# power_supply.net
KiCad netlist of a schematic drawn in Altium Designer
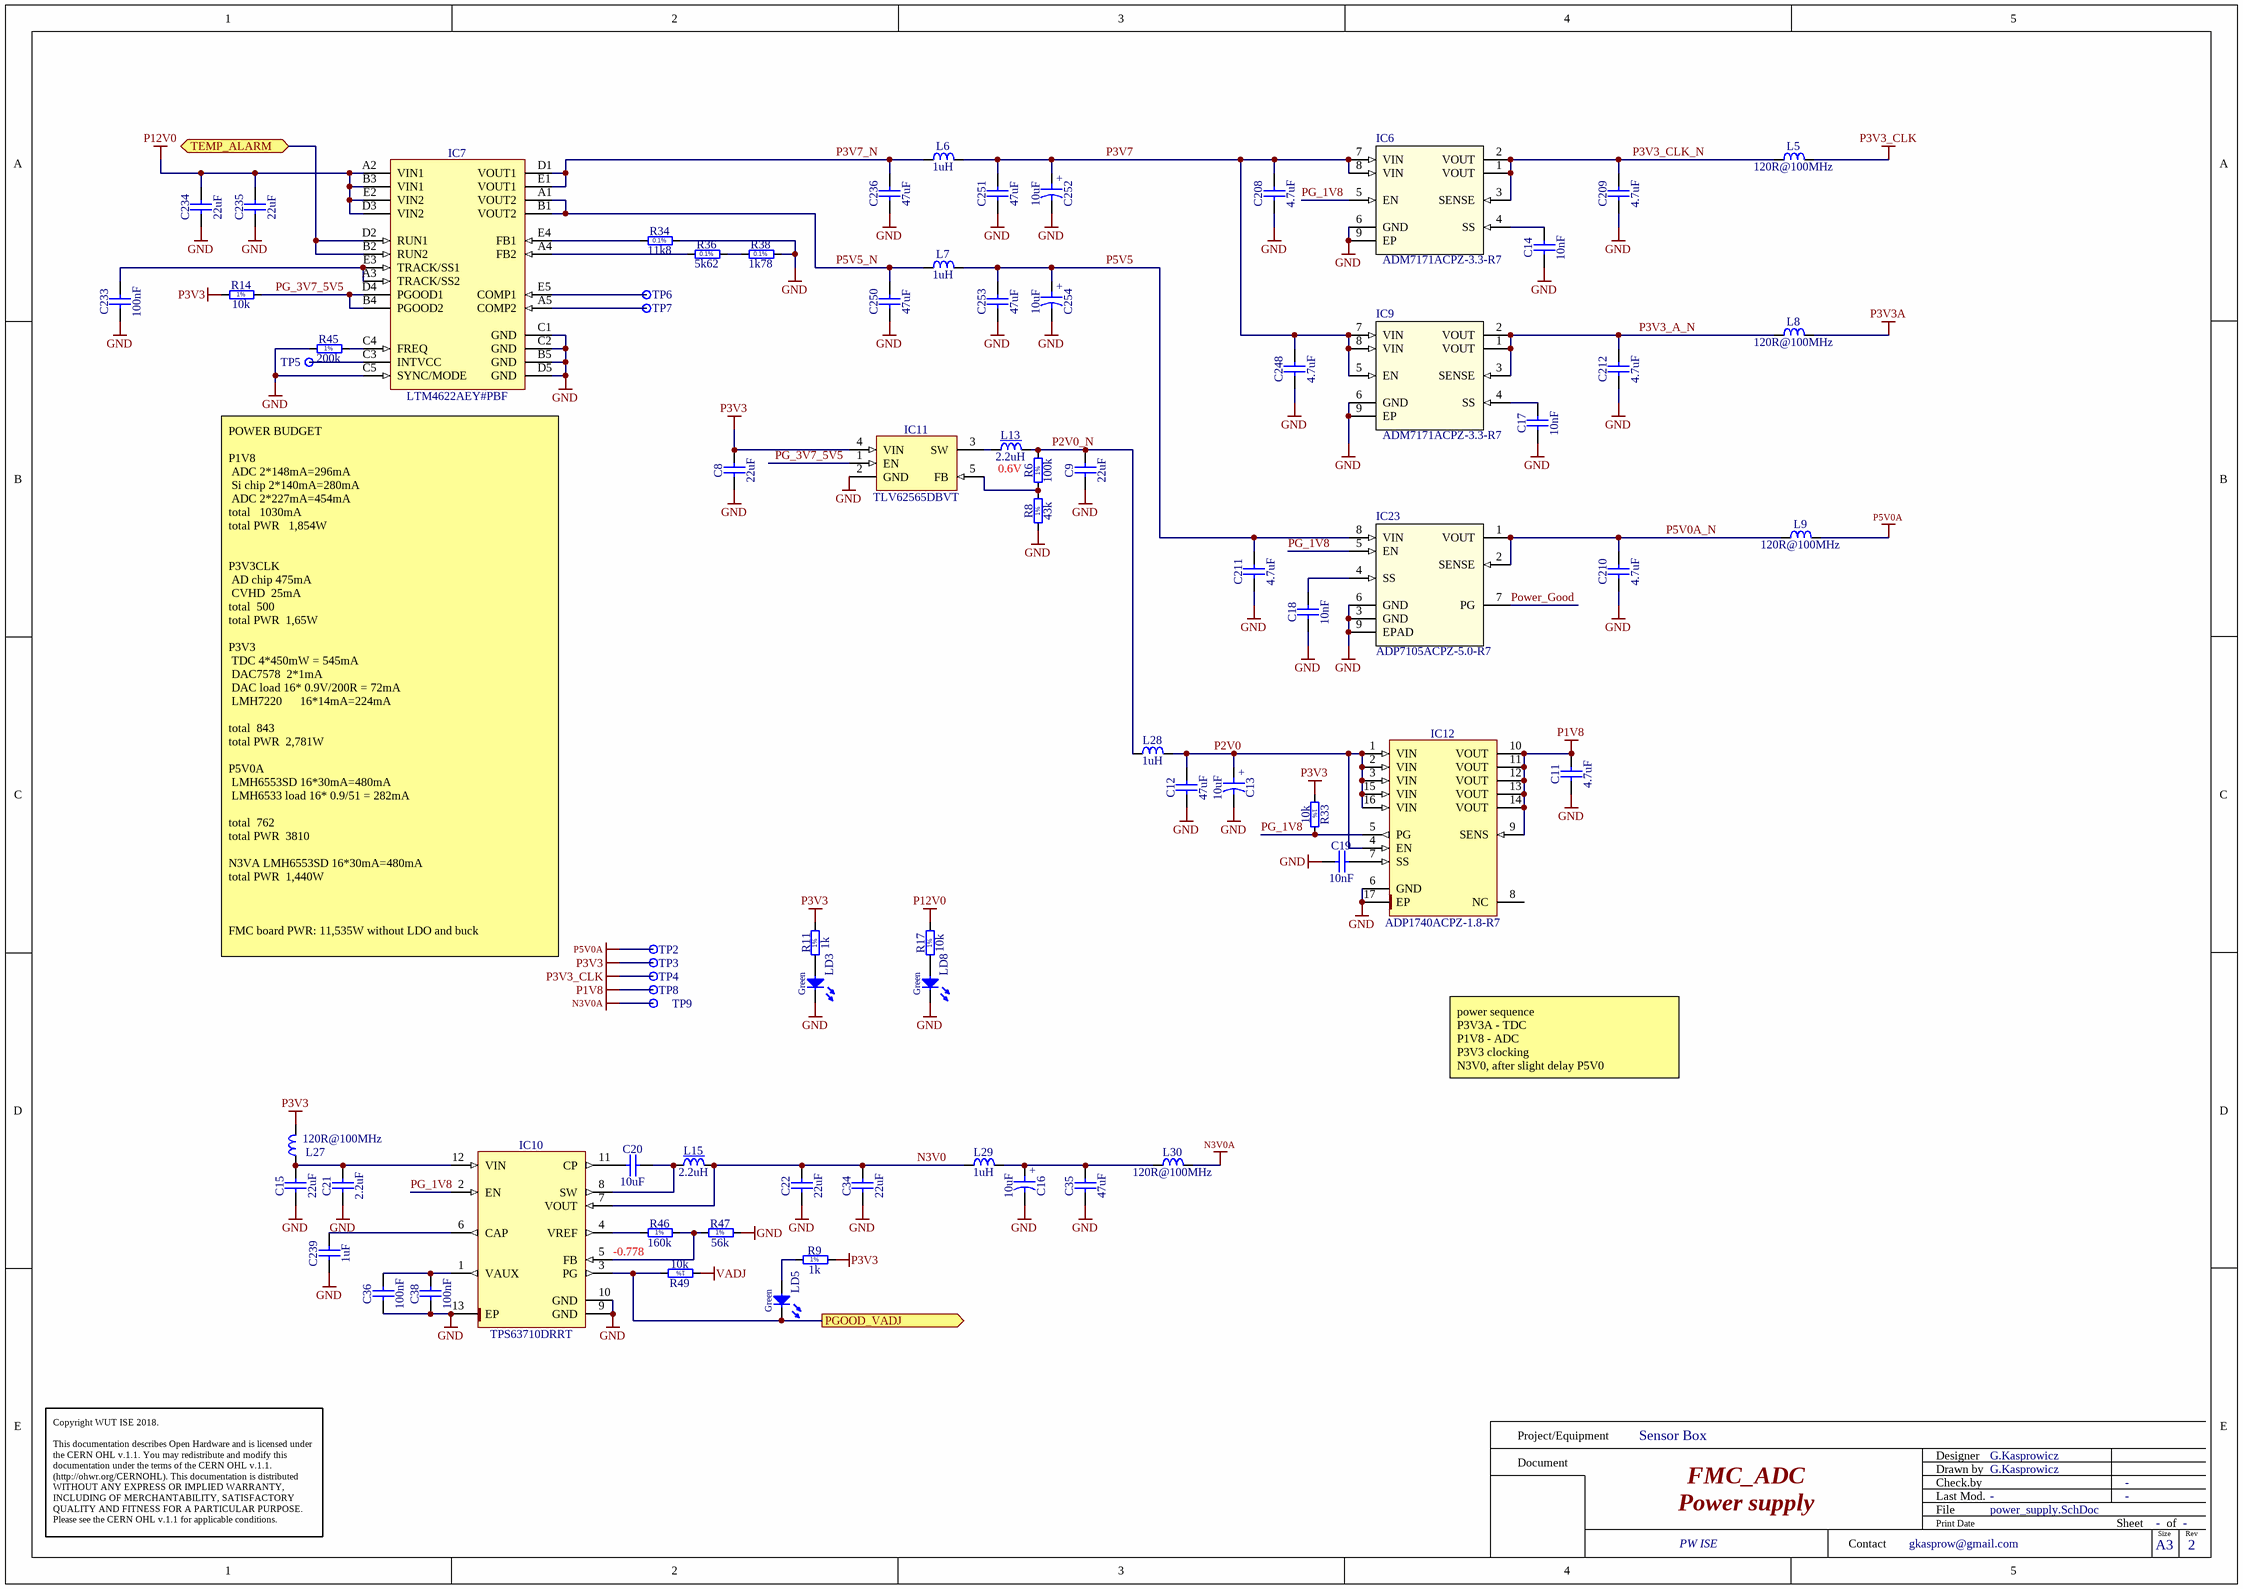
[diagram p0: power_supply.SchDoc]

(export (version "E")
  (design (tool "Eeschema 10.0.6"))
  (components
    (comp (ref "C8")
      (value "22uF")
      (footprint "CAPC2012X135N")
      (description "Non-polarised capacitor")
      (fields
        (field (name "PART NUMBER") "CC0805_22UF_16V_10%_X5R")
        (field (name "VOLTAGE") "16V")
        (field (name "AUTHOR") "CERN DEM JLC")
      )
      (libsource (lib "Capacitors") (part "Capacitor - non polarized"))
    )
    (comp (ref "C9")
      (value "22uF")
      (footprint "CAPC2012X135N")
      (description "Non-polarised capacitor")
      (fields
        (field (name "PART NUMBER") "CC0805_22UF_16V_10%_X5R")
        (field (name "VOLTAGE") "16V")
        (field (name "AUTHOR") "CERN DEM JLC")
      )
      (libsource (lib "Capacitors") (part "Capacitor - non polarized"))
    )
    (comp (ref "C11")
      (value "4.7uF")
      (footprint "CAPC1709X95N")
      (description "Non-polarised capacitor")
      (fields
        (field (name "PART NUMBER") "CC0603_4.7UF_16V_10%_X5R")
        (field (name "VOLTAGE") "16V")
        (field (name "AUTHOR") "CERN DEM JLC")
      )
      (libsource (lib "Capacitors") (part "Capacitor - non polarized"))
    )
    (comp (ref "C12")
      (value "47uF")
      (footprint "CAPC3225X270N")
      (description "Non-polarised capacitor")
      (fields
        (field (name "PART NUMBER") "CC1210_47UF_10V_20%_X5R")
        (field (name "VOLTAGE") "10V")
        (field (name "AUTHOR") "CERN DEM JLC")
      )
      (libsource (lib "Capacitors") (part "Capacitor - non polarized"))
    )
    (comp (ref "C13")
      (value "10uF")
      (footprint "CAPMP3216X180N")
      (description "Polarised capacitor")
      (fields
        (field (name "PART NUMBER") "CTE3216-18_10UF_10V_10%_LESR1800")
        (field (name "VOLTAGE") "10V")
        (field (name "AUTHOR") "CERN DEM JLC")
      )
      (libsource (lib "Capacitors") (part "Capacitor - polarized"))
    )
    (comp (ref "C14")
      (value "10nF")
      (footprint "CAPC1005X55N")
      (description "Non-polarised capacitor")
      (fields
        (field (name "PART NUMBER") "CC0402_10NF_16V_10%_X7R")
        (field (name "VOLTAGE") "16V")
        (field (name "AUTHOR") "CERN DEM JLC")
      )
      (libsource (lib "Capacitors") (part "Capacitor - non polarized"))
    )
    (comp (ref "C15")
      (value "22uF")
      (footprint "CAPC2012X135N")
      (description "Non-polarised capacitor")
      (fields
        (field (name "PART NUMBER") "CC0805_22UF_16V_10%_X5R")
        (field (name "VOLTAGE") "16V")
        (field (name "AUTHOR") "CERN DEM JLC")
      )
      (libsource (lib "Capacitors") (part "Capacitor - non polarized"))
    )
    (comp (ref "C16")
      (value "10uF")
      (footprint "CAPMP3216X180N")
      (description "Polarised capacitor")
      (fields
        (field (name "PART NUMBER") "CTE3216-18_10UF_10V_10%_LESR1800")
        (field (name "VOLTAGE") "10V")
        (field (name "AUTHOR") "CERN DEM JLC")
      )
      (libsource (lib "Capacitors") (part "Capacitor - polarized"))
    )
    (comp (ref "C17")
      (value "10nF")
      (footprint "CAPC1005X55N")
      (description "Non-polarised capacitor")
      (fields
        (field (name "PART NUMBER") "CC0402_10NF_16V_10%_X7R")
        (field (name "VOLTAGE") "16V")
        (field (name "AUTHOR") "CERN DEM JLC")
      )
      (libsource (lib "Capacitors") (part "Capacitor - non polarized"))
    )
    (comp (ref "C18")
      (value "10nF")
      (footprint "CAPC1005X55N")
      (description "Non-polarised capacitor")
      (fields
        (field (name "PART NUMBER") "CC0402_10NF_16V_10%_X7R")
        (field (name "VOLTAGE") "16V")
        (field (name "AUTHOR") "CERN DEM JLC")
      )
      (libsource (lib "Capacitors") (part "Capacitor - non polarized"))
    )
    (comp (ref "C19")
      (value "10nF")
      (footprint "CAPC1005X55N")
      (description "Non-polarised capacitor")
      (fields
        (field (name "PART NUMBER") "CC0402_10NF_16V_10%_X7R")
        (field (name "VOLTAGE") "16V")
        (field (name "AUTHOR") "CERN DEM JLC")
      )
      (libsource (lib "Capacitors") (part "Capacitor - non polarized"))
    )
    (comp (ref "C20")
      (value "10uF")
      (footprint "CAPC2012X135N")
      (description "Non-polarised capacitor")
      (fields
        (field (name "PART NUMBER") "CC0805_10UF_16V_10%_X5R")
        (field (name "VOLTAGE") "16V")
        (field (name "AUTHOR") "CERN DEM JLC")
      )
      (libsource (lib "Capacitors") (part "Capacitor - non polarized"))
    )
    (comp (ref "C21")
      (value "2.2uF")
      (footprint "CAPC1608X87N")
      (description "Non-polarised capacitor")
      (fields
        (field (name "PART NUMBER") "CC0603_2.2UF_16V_10%_X5R")
        (field (name "VOLTAGE") "16V")
        (field (name "AUTHOR") "CERN DEM JLC")
      )
      (libsource (lib "Capacitors") (part "Capacitor - non polarized"))
    )
    (comp (ref "C22")
      (value "22uF")
      (footprint "CAPC2012X135N")
      (description "Non-polarised capacitor")
      (fields
        (field (name "PART NUMBER") "CC0805_22UF_16V_10%_X5R")
        (field (name "VOLTAGE") "16V")
        (field (name "AUTHOR") "CERN DEM JLC")
      )
      (libsource (lib "Capacitors") (part "Capacitor - non polarized"))
    )
    (comp (ref "C34")
      (value "22uF")
      (footprint "CAPC2012X135N")
      (description "Non-polarised capacitor")
      (fields
        (field (name "PART NUMBER") "CC0805_22UF_16V_10%_X5R")
        (field (name "VOLTAGE") "16V")
        (field (name "AUTHOR") "CERN DEM JLC")
      )
      (libsource (lib "Capacitors") (part "Capacitor - non polarized"))
    )
    (comp (ref "C35")
      (value "47uF")
      (footprint "CAPC3225X270N")
      (description "Non-polarised capacitor")
      (fields
        (field (name "PART NUMBER") "CC1210_47UF_10V_20%_X5R")
        (field (name "VOLTAGE") "10V")
        (field (name "AUTHOR") "CERN DEM JLC")
      )
      (libsource (lib "Capacitors") (part "Capacitor - non polarized"))
    )
    (comp (ref "C36")
      (value "100nF")
      (footprint "CAPC1005X55N")
      (description "Non-polarised capacitor")
      (fields
        (field (name "PART NUMBER") "CC0402_100NF_16V_10%_X5R")
        (field (name "VOLTAGE") "16V")
        (field (name "AUTHOR") "CERN DEM JLC")
      )
      (libsource (lib "Capacitors") (part "Capacitor - non polarized"))
    )
    (comp (ref "C38")
      (value "100nF")
      (footprint "CAPC1005X55N")
      (description "Non-polarised capacitor")
      (fields
        (field (name "PART NUMBER") "CC0402_100NF_16V_10%_X5R")
        (field (name "VOLTAGE") "16V")
        (field (name "AUTHOR") "CERN DEM JLC")
      )
      (libsource (lib "Capacitors") (part "Capacitor - non polarized"))
    )
    (comp (ref "C208")
      (value "4.7uF")
      (footprint "CAPC1709X95N")
      (description "Non-polarised capacitor")
      (fields
        (field (name "PART NUMBER") "CC0603_4.7UF_16V_10%_X5R")
        (field (name "VOLTAGE") "16V")
        (field (name "AUTHOR") "CERN DEM JLC")
      )
      (libsource (lib "Capacitors") (part "Capacitor - non polarized"))
    )
    (comp (ref "C209")
      (value "4.7uF")
      (footprint "CAPC1709X95N")
      (description "Non-polarised capacitor")
      (fields
        (field (name "PART NUMBER") "CC0603_4.7UF_16V_10%_X5R")
        (field (name "VOLTAGE") "16V")
        (field (name "AUTHOR") "CERN DEM JLC")
      )
      (libsource (lib "Capacitors") (part "Capacitor - non polarized"))
    )
    (comp (ref "C210")
      (value "4.7uF")
      (footprint "CAPC1709X95N")
      (description "Non-polarised capacitor")
      (fields
        (field (name "PART NUMBER") "CC0603_4.7UF_16V_10%_X5R")
        (field (name "VOLTAGE") "16V")
        (field (name "AUTHOR") "CERN DEM JLC")
      )
      (libsource (lib "Capacitors") (part "Capacitor - non polarized"))
    )
    (comp (ref "C211")
      (value "4.7uF")
      (footprint "CAPC1709X95N")
      (description "Non-polarised capacitor")
      (fields
        (field (name "PART NUMBER") "CC0603_4.7UF_16V_10%_X5R")
        (field (name "VOLTAGE") "16V")
        (field (name "AUTHOR") "CERN DEM JLC")
      )
      (libsource (lib "Capacitors") (part "Capacitor - non polarized"))
    )
    (comp (ref "C212")
      (value "4.7uF")
      (footprint "CAPC1709X95N")
      (description "Non-polarised capacitor")
      (fields
        (field (name "PART NUMBER") "CC0603_4.7UF_16V_10%_X5R")
        (field (name "VOLTAGE") "16V")
        (field (name "AUTHOR") "CERN DEM JLC")
      )
      (libsource (lib "Capacitors") (part "Capacitor - non polarized"))
    )
    (comp (ref "C233")
      (value "100nF")
      (footprint "CAPC1005X55N")
      (description "Non-polarised capacitor")
      (fields
        (field (name "PART NUMBER") "CC0402_100NF_16V_10%_X5R")
        (field (name "VOLTAGE") "16V")
        (field (name "AUTHOR") "CERN DEM JLC")
      )
      (libsource (lib "Capacitors") (part "Capacitor - non polarized"))
    )
    (comp (ref "C234")
      (value "22uF")
      (footprint "CAPC2012X135N")
      (description "Non-polarised capacitor")
      (fields
        (field (name "PART NUMBER") "CC0805_22UF_16V_10%_X5R")
        (field (name "VOLTAGE") "16V")
        (field (name "AUTHOR") "CERN DEM JLC")
      )
      (libsource (lib "Capacitors") (part "Capacitor - non polarized"))
    )
    (comp (ref "C235")
      (value "22uF")
      (footprint "CAPC2012X135N")
      (description "Non-polarised capacitor")
      (fields
        (field (name "PART NUMBER") "CC0805_22UF_16V_10%_X5R")
        (field (name "VOLTAGE") "16V")
        (field (name "AUTHOR") "CERN DEM JLC")
      )
      (libsource (lib "Capacitors") (part "Capacitor - non polarized"))
    )
    (comp (ref "C236")
      (value "47uF")
      (footprint "CAPC3225X270N")
      (description "Non-polarised capacitor")
      (fields
        (field (name "PART NUMBER") "CC1210_47UF_10V_20%_X5R")
        (field (name "VOLTAGE") "10V")
        (field (name "AUTHOR") "CERN DEM JLC")
      )
      (libsource (lib "Capacitors") (part "Capacitor - non polarized"))
    )
    (comp (ref "C239")
      (value "1uF")
      (footprint "CAPC1608X87N")
      (description "Non-polarised capacitor")
      (fields
        (field (name "PART NUMBER") "CC0603_1UF_16V_10%_X7R")
        (field (name "VOLTAGE") "16V")
        (field (name "AUTHOR") "CERN DEM JLC")
      )
      (libsource (lib "Capacitors") (part "Capacitor - non polarized"))
    )
    (comp (ref "C248")
      (value "4.7uF")
      (footprint "CAPC1709X95N")
      (description "Non-polarised capacitor")
      (fields
        (field (name "PART NUMBER") "CC0603_4.7UF_16V_10%_X5R")
        (field (name "VOLTAGE") "16V")
        (field (name "AUTHOR") "CERN DEM JLC")
      )
      (libsource (lib "Capacitors") (part "Capacitor - non polarized"))
    )
    (comp (ref "C250")
      (value "47uF")
      (footprint "CAPC3225X270N")
      (description "Non-polarised capacitor")
      (fields
        (field (name "PART NUMBER") "CC1210_47UF_10V_20%_X5R")
        (field (name "VOLTAGE") "10V")
        (field (name "AUTHOR") "CERN DEM JLC")
      )
      (libsource (lib "Capacitors") (part "Capacitor - non polarized"))
    )
    (comp (ref "C251")
      (value "47uF")
      (footprint "CAPC3225X270N")
      (description "Non-polarised capacitor")
      (fields
        (field (name "PART NUMBER") "CC1210_47UF_10V_20%_X5R")
        (field (name "VOLTAGE") "10V")
        (field (name "AUTHOR") "CERN DEM JLC")
      )
      (libsource (lib "Capacitors") (part "Capacitor - non polarized"))
    )
    (comp (ref "C252")
      (value "10uF")
      (footprint "CAPMP3216X180N")
      (description "Polarised capacitor")
      (fields
        (field (name "PART NUMBER") "CTE3216-18_10UF_10V_10%_LESR1800")
        (field (name "VOLTAGE") "10V")
        (field (name "AUTHOR") "CERN DEM JLC")
      )
      (libsource (lib "Capacitors") (part "Capacitor - polarized"))
    )
    (comp (ref "C253")
      (value "47uF")
      (footprint "CAPC3225X270N")
      (description "Non-polarised capacitor")
      (fields
        (field (name "PART NUMBER") "CC1210_47UF_10V_20%_X5R")
        (field (name "VOLTAGE") "10V")
        (field (name "AUTHOR") "CERN DEM JLC")
      )
      (libsource (lib "Capacitors") (part "Capacitor - non polarized"))
    )
    (comp (ref "C254")
      (value "10uF")
      (footprint "CAPMP3216X180N")
      (description "Polarised capacitor")
      (fields
        (field (name "PART NUMBER") "CTE3216-18_10UF_10V_10%_LESR1800")
        (field (name "VOLTAGE") "10V")
        (field (name "AUTHOR") "CERN DEM JLC")
      )
      (libsource (lib "Capacitors") (part "Capacitor - polarized"))
    )
    (comp (ref "IC6")
      (value "ADM7171ACPZ-3.3-R7")
      (footprint "CP_8_21-L")
      (description "6.5 V, 1 A, Ultralow Noise, High PSRR,  Fast Transient Response CMOS LDO")
      (fields (field (name "MANUFACTURER") "Analog Devices"))
      (libsource (lib "FMC_ADC") (part "ADM7171ACPZ-3.3-R7"))
    )
    (comp (ref "IC7")
      (value "LTM4622AEY#PBF")
      (footprint "BGA25C127P5X5_625X625X262")
      (description "3.6V-20V To 1.5V-12V, Dual 2A or Single 4A  Ultrathin Step-Down DC/DC µModule Regulator")
      (fields (field (name "MANUFACTURER") "LINEAR TECHNOLOGY") (field (name "AUTHOR") "CERN DEM MR"))
      (libsource (lib "ICs And Semiconductors") (part "LTM4622A"))
    )
    (comp (ref "IC9")
      (value "ADM7171ACPZ-3.3-R7")
      (footprint "CP_8_21-L")
      (description "6.5 V, 1 A, Ultralow Noise, High PSRR,  Fast Transient Response CMOS LDO")
      (fields (field (name "MANUFACTURER") "Analog Devices"))
      (libsource (lib "FMC_ADC") (part "ADM7171ACPZ-3.3-R7"))
    )
    (comp (ref "IC10")
      (value "TPS63710DRRT")
      (footprint "SON50P300X80_HS-13N")
      (description "Low Noise, 1A Synchronous Inverting Buck Converter in 3x3 WSON Package")
      (fields (field (name "MANUFACTURER") "TEXAS INSTRUMENTS") (field (name "AUTHOR") "GK"))
      (libsource (lib "LIBRARY_SCH") (part "PM_TPS6371"))
    )
    (comp (ref "IC11")
      (value "TLV62565DBVT")
      (footprint "SOT95P280X145-5N")
      (description "1.5A High Efficiency Step-Down Converter, Adjustable Output Voltage")
      (fields (field (name "MANUFACTURER") "TEXAS INSTRUMENTS") (field (name "AUTHOR") "CERN DEM JMW"))
      (libsource (lib "ICs And Semiconductors") (part "TLV62565"))
    )
    (comp (ref "IC12")
      (value "ADP1740ACPZ-1.8-R7")
      (footprint "QFN65P400X400X100-17N-S225")
      (description "2A, Low-Dropout Linear Regulator")
      (fields (field (name "MANUFACTURER") "ANALOG DEVICES") (field (name "AUTHOR") "CERN DEM JLC"))
      (libsource (lib "ICs And Semiconductors") (part "ADP1740"))
    )
    (comp (ref "IC23")
      (value "ADP7105ACPZ-5.0-R7")
      (footprint "CP_8_5")
      (description "20 V, 500 mA, Low Noise LDO Regulator  with Soft Start")
      (fields (field (name "MANUFACTURER") "Analog Devices"))
      (libsource (lib "FMC_ADC") (part "ADP7105ACPZ-5.0-R7"))
    )
    (comp (ref "L5")
      (value "120R@100MHz")
      (footprint "INDC1608X65N")
      (description "Inductor")
      (fields
        (field (name "PART NUMBER") "IND0603_MURATA_BLM18SG121TN1D")
        (field (name "POWER") "3A")
        (field (name "AUTHOR") "CERN DEM JLC")
      )
      (libsource (lib "Inductors & Transformers") (part "Inductor"))
    )
    (comp (ref "L6")
      (value "1uH")
      (footprint "INDC2620X100N")
      (description "Inductor")
      (fields
        (field (name "PART NUMBER") "IND1008_1UH_20%_WURTH_74479787210B")
        (field (name "POWER") "1.95A")
        (field (name "AUTHOR") "CERN DEM JLC")
      )
      (libsource (lib "Inductors & Transformers") (part "Inductor"))
    )
    (comp (ref "L7")
      (value "1uH")
      (footprint "INDC2620X100N")
      (description "Inductor")
      (fields
        (field (name "PART NUMBER") "IND1008_1UH_20%_WURTH_74479787210B")
        (field (name "POWER") "1.95A")
        (field (name "AUTHOR") "CERN DEM JLC")
      )
      (libsource (lib "Inductors & Transformers") (part "Inductor"))
    )
    (comp (ref "L8")
      (value "120R@100MHz")
      (footprint "INDC1608X65N")
      (description "Inductor")
      (fields
        (field (name "PART NUMBER") "IND0603_MURATA_BLM18SG121TN1D")
        (field (name "POWER") "3A")
        (field (name "AUTHOR") "CERN DEM JLC")
      )
      (libsource (lib "Inductors & Transformers") (part "Inductor"))
    )
    (comp (ref "L9")
      (value "120R@100MHz")
      (footprint "INDC1608X65N")
      (description "Inductor")
      (fields
        (field (name "PART NUMBER") "IND0603_MURATA_BLM18SG121TN1D")
        (field (name "POWER") "3A")
        (field (name "AUTHOR") "CERN DEM JLC")
      )
      (libsource (lib "Inductors & Transformers") (part "Inductor"))
    )
    (comp (ref "L13")
      (value "2.2uH")
      (footprint "IND_WURTH_WE-TPC_4828")
      (description "Inductor With Core")
      (fields
        (field (name "PART NUMBER") "IND_2.2UH_30%_WURTH_WE-TPC_7440430022")
        (field (name "POWER") "2.5A")
        (field (name "AUTHOR") "CERN DEM JLC")
      )
      (libsource (lib "Inductors & Transformers") (part "Inductor With Magnetic core"))
    )
    (comp (ref "L15")
      (value "2.2uH")
      (footprint "IND_WURTH_WE-TPC_4828")
      (description "Inductor With Core")
      (fields
        (field (name "PART NUMBER") "IND_2.2UH_30%_WURTH_WE-TPC_7440430022")
        (field (name "POWER") "2.5A")
        (field (name "AUTHOR") "CERN DEM JLC")
      )
      (libsource (lib "Inductors & Transformers") (part "Inductor With Magnetic core"))
    )
    (comp (ref "L27")
      (value "120R@100MHz")
      (footprint "INDC1608X65N")
      (description "Inductor")
      (fields
        (field (name "PART NUMBER") "IND0603_MURATA_BLM18SG121TN1D")
        (field (name "POWER") "3A")
        (field (name "AUTHOR") "CERN DEM JLC")
      )
      (libsource (lib "") (part "Inductor_1"))
    )
    (comp (ref "L28")
      (value "1uH")
      (footprint "INDC2620X100N")
      (description "Inductor")
      (fields
        (field (name "PART NUMBER") "IND1008_1UH_20%_WURTH_74479787210B")
        (field (name "POWER") "1.95A")
        (field (name "AUTHOR") "CERN DEM JLC")
      )
      (libsource (lib "Inductors & Transformers") (part "Inductor"))
    )
    (comp (ref "L29")
      (value "1uH")
      (footprint "INDC2620X100N")
      (description "Inductor")
      (fields
        (field (name "PART NUMBER") "IND1008_1UH_20%_WURTH_74479787210B")
        (field (name "POWER") "1.95A")
        (field (name "AUTHOR") "CERN DEM JLC")
      )
      (libsource (lib "Inductors & Transformers") (part "Inductor"))
    )
    (comp (ref "L30")
      (value "120R@100MHz")
      (footprint "INDC1608X65N")
      (description "Inductor")
      (fields
        (field (name "PART NUMBER") "IND0603_MURATA_BLM18SG121TN1D")
        (field (name "POWER") "3A")
        (field (name "AUTHOR") "CERN DEM JLC")
      )
      (libsource (lib "Inductors & Transformers") (part "Inductor"))
    )
    (comp (ref "LD3")
      (value "Green")
      (footprint "LED_KINGBRIGHT_KPH-1608CGCK")
      (description "LED Green 1C 2A")
      (fields
        (field (name "PART NUMBER") "LED_KINGBRIGHT_KPH-1608CGCK")
        (field (name "MANUFACTURER") "KINGBRIGHT")
        (field (name "AUTHOR") "CERN DEM JLC")
      )
      (libsource (lib "ICs And Semiconductors") (part "LED Green 1C 2A"))
    )
    (comp (ref "LD5")
      (value "Green")
      (footprint "LED_KINGBRIGHT_KPH-1608CGCK")
      (description "LED Green 1C 2A")
      (fields
        (field (name "PART NUMBER") "LED_KINGBRIGHT_KPH-1608CGCK")
        (field (name "MANUFACTURER") "KINGBRIGHT")
        (field (name "AUTHOR") "CERN DEM JLC")
      )
      (libsource (lib "ICs And Semiconductors") (part "LED Green 1C 2A"))
    )
    (comp (ref "LD8")
      (value "Green")
      (footprint "LED_KINGBRIGHT_KPH-1608CGCK")
      (description "LED Green 1C 2A")
      (fields
        (field (name "PART NUMBER") "LED_KINGBRIGHT_KPH-1608CGCK")
        (field (name "MANUFACTURER") "KINGBRIGHT")
        (field (name "AUTHOR") "CERN DEM JLC")
      )
      (libsource (lib "ICs And Semiconductors") (part "LED Green 1C 2A"))
    )
    (comp (ref "R6")
      (value "100k")
      (footprint "RESC1005X40N")
      (description "Resistor - 1%")
      (fields
        (field (name "PART NUMBER") "R0402_100K_1%_0.0625W_100PPM")
        (field (name "POWER") "0.0625W")
        (field (name "AUTHOR") "CERN DEM JLC")
      )
      (libsource (lib "Resistors") (part "Resistor - 1%"))
    )
    (comp (ref "R8")
      (value "43k")
      (footprint "RESC1005X40N")
      (description "Resistor - 1%")
      (fields
        (field (name "PART NUMBER") "R0402_43K_1%_0.0625W_100PPM")
        (field (name "POWER") "0.0625W")
        (field (name "AUTHOR") "CERN DEM JLC")
      )
      (libsource (lib "Resistors") (part "Resistor - 1%"))
    )
    (comp (ref "R9")
      (value "1k")
      (footprint "RESC1005X40N")
      (description "Resistor - 1%")
      (fields
        (field (name "PART NUMBER") "R0402_1K_1%_0.0625W_100PPM")
        (field (name "POWER") "0.0625W")
        (field (name "AUTHOR") "CERN DEM JLC")
      )
      (libsource (lib "Resistors") (part "Resistor - 1%"))
    )
    (comp (ref "R11")
      (value "1k")
      (footprint "RESC1005X40N")
      (description "Resistor - 1%")
      (fields
        (field (name "PART NUMBER") "R0402_1K_1%_0.0625W_100PPM")
        (field (name "POWER") "0.0625W")
        (field (name "AUTHOR") "CERN DEM JLC")
      )
      (libsource (lib "Resistors") (part "Resistor - 1%"))
    )
    (comp (ref "R14")
      (value "10k")
      (footprint "RESC1005X40N")
      (description "Resistor - 1%")
      (fields
        (field (name "PART NUMBER") "R0402_10K_1%_0.0625W_100PPM")
        (field (name "POWER") "0.0625W")
        (field (name "AUTHOR") "CERN DEM JLC")
      )
      (libsource (lib "Resistors") (part "Resistor - 1%"))
    )
    (comp (ref "R17")
      (value "10k")
      (footprint "RESC1005X40N")
      (description "Resistor - 1%")
      (fields
        (field (name "PART NUMBER") "R0402_10K_1%_0.0625W_100PPM")
        (field (name "POWER") "0.0625W")
        (field (name "AUTHOR") "CERN DEM JLC")
      )
      (libsource (lib "Resistors") (part "Resistor - 1%"))
    )
    (comp (ref "R33")
      (value "10k")
      (footprint "RESC1005X40N")
      (description "Resistor - 1%")
      (fields
        (field (name "PART NUMBER") "R0402_10K_1%_0.0625W_100PPM")
        (field (name "POWER") "0.0625W")
        (field (name "AUTHOR") "CERN DEM JLC")
      )
      (libsource (lib "Resistors") (part "Resistor - 1%"))
    )
    (comp (ref "R34")
      (value "11k8")
      (footprint "RESC1608X55N")
      (description "Resistor - 0.1%")
      (fields
        (field (name "PART NUMBER") "R0603_11K8_0.1%_0.063W_10PPM")
        (field (name "POWER") "0.063W")
        (field (name "AUTHOR") "CERN DEM JLC")
      )
      (libsource (lib "Resistors") (part "Resistor - 0.1%"))
    )
    (comp (ref "R36")
      (value "5k62")
      (footprint "RESC1608X55N")
      (description "Resistor - 0.1%")
      (fields
        (field (name "PART NUMBER") "R0603_5K62_0.1%_0.063W_10PPM")
        (field (name "POWER") "0.063W")
        (field (name "AUTHOR") "CERN DEM JLC")
      )
      (libsource (lib "Resistors") (part "Resistor - 0.1%"))
    )
    (comp (ref "R38")
      (value "1k78")
      (footprint "RESC1608X55N")
      (description "Resistor - 0.1%")
      (fields
        (field (name "PART NUMBER") "R0603_1K78_0.1%_0.063W_10PPM")
        (field (name "POWER") "0.063W")
        (field (name "AUTHOR") "CERN DEM JLC")
      )
      (libsource (lib "Resistors") (part "Resistor - 0.1%"))
    )
    (comp (ref "R45")
      (value "200k")
      (footprint "RESC1005X40N")
      (description "Resistor - 1%")
      (fields
        (field (name "PART NUMBER") "R0402_200K_1%_0.0625W_100PPM")
        (field (name "POWER") "0.0625W")
        (field (name "AUTHOR") "CERN DEM JLC")
      )
      (libsource (lib "Resistors") (part "Resistor - 1%"))
    )
    (comp (ref "R46")
      (value "160k")
      (footprint "RESC1005X40N")
      (description "Resistor - 1%")
      (fields
        (field (name "PART NUMBER") "R0402_160K_1%_0.0625W_100PPM")
        (field (name "POWER") "0.0625W")
        (field (name "AUTHOR") "CERN DEM JLC")
      )
      (libsource (lib "Resistors") (part "Resistor - 1%"))
    )
    (comp (ref "R47")
      (value "56k")
      (footprint "RESC1005X40N")
      (description "Resistor - 1%")
      (fields
        (field (name "PART NUMBER") "R0402_56K_1%_0.0625W_100PPM")
        (field (name "POWER") "0.0625W")
        (field (name "AUTHOR") "CERN DEM JLC")
      )
      (libsource (lib "Resistors") (part "Resistor - 1%"))
    )
    (comp (ref "R49")
      (value "10k")
      (footprint "RESC1005X40N")
      (description "Resistor - 1%")
      (fields
        (field (name "PART NUMBER") "R0402_10K_1%_0.0625W_100PPM")
        (field (name "POWER") "0.0625W")
        (field (name "AUTHOR") "CERN DEM JLC")
      )
      (libsource (lib "Resistors") (part "Resistor - 1%"))
    )
    (comp (ref "TP2")
      (value "Test Point")
      (footprint "TPS62")
      (fields (field (name "PART NUMBER") "SMD_PAD_0.62X0.62MM") (field (name "AUTHOR") "CERN DEM JLC"))
      (libsource (lib "FMC_ADC") (part "Test Point"))
    )
    (comp (ref "TP3")
      (value "Test Point")
      (footprint "TPS62")
      (fields (field (name "PART NUMBER") "SMD_PAD_0.62X0.62MM") (field (name "AUTHOR") "CERN DEM JLC"))
      (libsource (lib "FMC_ADC") (part "Test Point"))
    )
    (comp (ref "TP4")
      (value "Test Point")
      (footprint "TPS62")
      (fields (field (name "PART NUMBER") "SMD_PAD_0.62X0.62MM") (field (name "AUTHOR") "CERN DEM JLC"))
      (libsource (lib "FMC_ADC") (part "Test Point"))
    )
    (comp (ref "TP5")
      (value "Test Point")
      (footprint "TPS62")
      (fields (field (name "PART NUMBER") "SMD_PAD_0.62X0.62MM") (field (name "AUTHOR") "CERN DEM JLC"))
      (libsource (lib "FMC_ADC") (part "Test Point"))
    )
    (comp (ref "TP6")
      (value "Test Point")
      (footprint "TPS62")
      (fields (field (name "PART NUMBER") "SMD_PAD_0.62X0.62MM") (field (name "AUTHOR") "CERN DEM JLC"))
      (libsource (lib "FMC_ADC") (part "Test Point"))
    )
    (comp (ref "TP7")
      (value "Test Point")
      (footprint "TPS62")
      (fields (field (name "PART NUMBER") "SMD_PAD_0.62X0.62MM") (field (name "AUTHOR") "CERN DEM JLC"))
      (libsource (lib "FMC_ADC") (part "Test Point"))
    )
    (comp (ref "TP8")
      (value "Test Point")
      (footprint "TPS62")
      (fields (field (name "PART NUMBER") "SMD_PAD_0.62X0.62MM") (field (name "AUTHOR") "CERN DEM JLC"))
      (libsource (lib "FMC_ADC") (part "Test Point"))
    )
    (comp (ref "TP9")
      (value "Test Point")
      (footprint "TPS62")
      (fields (field (name "PART NUMBER") "SMD_PAD_0.62X0.62MM") (field (name "AUTHOR") "CERN DEM JLC"))
      (libsource (lib "FMC_ADC") (part "Test Point"))
    )
  )
  (nets
    (net (code "1") (name "/N3V0") (class "Default")
      (node (ref "C22") (pin "2") (pinfunction "2_2") (pintype "passive"))
      (node (ref "C34") (pin "2") (pinfunction "2_2") (pintype "passive"))
      (node (ref "IC10") (pin "7") (pinfunction "VOUT_7") (pintype "input"))
      (node (ref "L15") (pin "2") (pinfunction "2_2") (pintype "passive"))
      (node (ref "L29") (pin "1") (pinfunction "1_1") (pintype "passive"))
    )
    (net (code "2") (name "/P2V0") (class "Default")
      (node (ref "C12") (pin "2") (pinfunction "2_2") (pintype "passive"))
      (node (ref "C13") (pin "1") (pinfunction "1_1") (pintype "passive"))
      (node (ref "IC12") (pin "1") (pinfunction "VIN_1") (pintype "input"))
      (node (ref "IC12") (pin "15") (pinfunction "VIN_15") (pintype "input"))
      (node (ref "IC12") (pin "16") (pinfunction "VIN_16") (pintype "input"))
      (node (ref "IC12") (pin "2") (pinfunction "VIN_2") (pintype "input"))
      (node (ref "IC12") (pin "3") (pinfunction "VIN_3") (pintype "input"))
      (node (ref "IC12") (pin "4") (pinfunction "EN_4") (pintype "input"))
      (node (ref "L28") (pin "2") (pinfunction "2_2") (pintype "passive"))
    )
    (net (code "3") (name "/P2V0_N") (class "Default")
      (node (ref "C9") (pin "2") (pinfunction "2_2") (pintype "passive"))
      (node (ref "L13") (pin "2") (pinfunction "2_2") (pintype "passive"))
      (node (ref "L28") (pin "1") (pinfunction "1_1") (pintype "passive"))
      (node (ref "R6") (pin "2") (pinfunction "2_2") (pintype "passive"))
    )
    (net (code "4") (name "/P3V3_A_N") (class "Default")
      (node (ref "C212") (pin "2") (pinfunction "2_2") (pintype "passive"))
      (node (ref "IC9") (pin "1") (pinfunction "VOUT_1") (pintype "power_in"))
      (node (ref "IC9") (pin "2") (pinfunction "VOUT_2") (pintype "power_in"))
      (node (ref "IC9") (pin "3") (pinfunction "SENSE_3") (pintype "input"))
      (node (ref "L8") (pin "1") (pinfunction "1_1") (pintype "passive"))
    )
    (net (code "5") (name "/P3V3_CLK_N") (class "Default")
      (node (ref "C209") (pin "2") (pinfunction "2_2") (pintype "passive"))
      (node (ref "IC6") (pin "1") (pinfunction "VOUT_1") (pintype "power_in"))
      (node (ref "IC6") (pin "2") (pinfunction "VOUT_2") (pintype "power_in"))
      (node (ref "IC6") (pin "3") (pinfunction "SENSE_3") (pintype "input"))
      (node (ref "L5") (pin "1") (pinfunction "1_1") (pintype "passive"))
    )
    (net (code "6") (name "/P3V7") (class "Default")
      (node (ref "C208") (pin "2") (pinfunction "2_2") (pintype "passive"))
      (node (ref "C248") (pin "2") (pinfunction "2_2") (pintype "passive"))
      (node (ref "C251") (pin "2") (pinfunction "2_2") (pintype "passive"))
      (node (ref "C252") (pin "1") (pinfunction "1_1") (pintype "passive"))
      (node (ref "IC6") (pin "7") (pinfunction "VIN_7") (pintype "input"))
      (node (ref "IC6") (pin "8") (pinfunction "VIN_8") (pintype "input"))
      (node (ref "IC9") (pin "5") (pinfunction "EN_5") (pintype "input"))
      (node (ref "IC9") (pin "7") (pinfunction "VIN_7") (pintype "input"))
      (node (ref "IC9") (pin "8") (pinfunction "VIN_8") (pintype "input"))
      (node (ref "L6") (pin "2") (pinfunction "2_2") (pintype "passive"))
    )
    (net (code "7") (name "/P3V7_N") (class "Default")
      (node (ref "C236") (pin "2") (pinfunction "2_2") (pintype "passive"))
      (node (ref "IC7") (pin "D1") (pinfunction "VOUT1_D1") (pintype "power_in"))
      (node (ref "IC7") (pin "E1") (pinfunction "VOUT1_E1") (pintype "power_in"))
      (node (ref "L6") (pin "1") (pinfunction "1_1") (pintype "passive"))
    )
    (net (code "8") (name "/P5V0A_N") (class "Default")
      (node (ref "C210") (pin "2") (pinfunction "2_2") (pintype "passive"))
      (node (ref "IC23") (pin "1") (pinfunction "VOUT_1") (pintype "power_in"))
      (node (ref "IC23") (pin "2") (pinfunction "SENSE_2") (pintype "input"))
      (node (ref "L9") (pin "1") (pinfunction "1_1") (pintype "passive"))
    )
    (net (code "9") (name "/P5V5") (class "Default")
      (node (ref "C211") (pin "2") (pinfunction "2_2") (pintype "passive"))
      (node (ref "C253") (pin "2") (pinfunction "2_2") (pintype "passive"))
      (node (ref "C254") (pin "1") (pinfunction "1_1") (pintype "passive"))
      (node (ref "IC23") (pin "8") (pinfunction "VIN_8") (pintype "input"))
      (node (ref "L7") (pin "2") (pinfunction "2_2") (pintype "passive"))
    )
    (net (code "10") (name "/P5V5_N") (class "Default")
      (node (ref "C250") (pin "2") (pinfunction "2_2") (pintype "passive"))
      (node (ref "IC7") (pin "A1") (pinfunction "VOUT2_A1") (pintype "power_in"))
      (node (ref "IC7") (pin "B1") (pinfunction "VOUT2_B1") (pintype "power_in"))
      (node (ref "L7") (pin "1") (pinfunction "1_1") (pintype "passive"))
    )
    (net (code "11") (name "/PGOOD_VADJ") (class "Default")
      (node (ref "IC10") (pin "3") (pinfunction "PG_3") (pintype "output"))
      (node (ref "LD5") (pin "1") (pinfunction "C_1") (pintype "passive"))
      (node (ref "R49") (pin "2") (pinfunction "2_2") (pintype "passive"))
    )
    (net (code "12") (name "/PG_1V8") (class "Default")
      (node (ref "IC10") (pin "2") (pinfunction "EN_2") (pintype "input"))
      (node (ref "IC12") (pin "5") (pinfunction "PG_5") (pintype "output"))
      (node (ref "IC23") (pin "5") (pinfunction "EN_5") (pintype "input"))
      (node (ref "IC6") (pin "5") (pinfunction "EN_5") (pintype "input"))
      (node (ref "R33") (pin "2") (pinfunction "2_2") (pintype "passive"))
    )
    (net (code "13") (name "/PG_3V7_5V5") (class "Default")
      (node (ref "IC11") (pin "1") (pinfunction "EN_1") (pintype "input"))
      (node (ref "IC7") (pin "B4") (pinfunction "PGOOD2_B4") (pintype "open_collector"))
      (node (ref "IC7") (pin "D4") (pinfunction "PGOOD1_D4") (pintype "open_collector"))
      (node (ref "R14") (pin "2") (pinfunction "2_2") (pintype "passive"))
    )
    (net (code "14") (name "/Power_Good") (class "Default")
      (node (ref "IC23") (pin "7") (pinfunction "PG_7") (pintype "open_collector"))
    )
    (net (code "15") (name "/TEMP_ALARM") (class "Default")
      (node (ref "IC7") (pin "B2") (pinfunction "RUN2_B2") (pintype "input"))
      (node (ref "IC7") (pin "D2") (pinfunction "RUN1_D2") (pintype "input"))
    )
    (net (code "16") (name "GND") (class "Default")
      (node (ref "C11") (pin "1") (pinfunction "1_1") (pintype "passive"))
      (node (ref "C12") (pin "1") (pinfunction "1_1") (pintype "passive"))
      (node (ref "C13") (pin "2") (pinfunction "2_2") (pintype "passive"))
      (node (ref "C14") (pin "1") (pinfunction "1_1") (pintype "passive"))
      (node (ref "C15") (pin "1") (pinfunction "1_1") (pintype "passive"))
      (node (ref "C16") (pin "2") (pinfunction "2_2") (pintype "passive"))
      (node (ref "C17") (pin "1") (pinfunction "1_1") (pintype "passive"))
      (node (ref "C18") (pin "1") (pinfunction "1_1") (pintype "passive"))
      (node (ref "C19") (pin "1") (pinfunction "1_1") (pintype "passive"))
      (node (ref "C208") (pin "1") (pinfunction "1_1") (pintype "passive"))
      (node (ref "C209") (pin "1") (pinfunction "1_1") (pintype "passive"))
      (node (ref "C21") (pin "1") (pinfunction "1_1") (pintype "passive"))
      (node (ref "C210") (pin "1") (pinfunction "1_1") (pintype "passive"))
      (node (ref "C211") (pin "1") (pinfunction "1_1") (pintype "passive"))
      (node (ref "C212") (pin "1") (pinfunction "1_1") (pintype "passive"))
      (node (ref "C22") (pin "1") (pinfunction "1_1") (pintype "passive"))
      (node (ref "C233") (pin "1") (pinfunction "1_1") (pintype "passive"))
      (node (ref "C234") (pin "1") (pinfunction "1_1") (pintype "passive"))
      (node (ref "C235") (pin "1") (pinfunction "1_1") (pintype "passive"))
      (node (ref "C236") (pin "1") (pinfunction "1_1") (pintype "passive"))
      (node (ref "C239") (pin "1") (pinfunction "1_1") (pintype "passive"))
      (node (ref "C248") (pin "1") (pinfunction "1_1") (pintype "passive"))
      (node (ref "C250") (pin "1") (pinfunction "1_1") (pintype "passive"))
      (node (ref "C251") (pin "1") (pinfunction "1_1") (pintype "passive"))
      (node (ref "C252") (pin "2") (pinfunction "2_2") (pintype "passive"))
      (node (ref "C253") (pin "1") (pinfunction "1_1") (pintype "passive"))
      (node (ref "C254") (pin "2") (pinfunction "2_2") (pintype "passive"))
      (node (ref "C34") (pin "1") (pinfunction "1_1") (pintype "passive"))
      (node (ref "C35") (pin "1") (pinfunction "1_1") (pintype "passive"))
      (node (ref "C36") (pin "1") (pinfunction "1_1") (pintype "passive"))
      (node (ref "C38") (pin "1") (pinfunction "1_1") (pintype "passive"))
      (node (ref "C8") (pin "1") (pinfunction "1_1") (pintype "passive"))
      (node (ref "C9") (pin "1") (pinfunction "1_1") (pintype "passive"))
      (node (ref "IC10") (pin "10") (pinfunction "GND_10") (pintype "power_in"))
      (node (ref "IC10") (pin "13") (pinfunction "EP_13") (pintype "power_in"))
      (node (ref "IC10") (pin "9") (pinfunction "GND_9") (pintype "power_in"))
      (node (ref "IC11") (pin "2") (pinfunction "GND_2") (pintype "power_in"))
      (node (ref "IC12") (pin "17") (pinfunction "EP_17") (pintype "power_in"))
      (node (ref "IC12") (pin "6") (pinfunction "GND_6") (pintype "power_in"))
      (node (ref "IC23") (pin "3") (pinfunction "GND_3") (pintype "power_in"))
      (node (ref "IC23") (pin "6") (pinfunction "GND_6") (pintype "power_in"))
      (node (ref "IC23") (pin "9") (pinfunction "EPAD_9") (pintype "power_in"))
      (node (ref "IC6") (pin "6") (pinfunction "GND_6") (pintype "passive"))
      (node (ref "IC6") (pin "9") (pinfunction "EP_9") (pintype "passive"))
      (node (ref "IC7") (pin "B5") (pinfunction "GND_B5") (pintype "power_in"))
      (node (ref "IC7") (pin "C1") (pinfunction "GND_C1") (pintype "power_in"))
      (node (ref "IC7") (pin "C2") (pinfunction "GND_C2") (pintype "power_in"))
      (node (ref "IC7") (pin "C5") (pinfunction "SYNC/MODE_C5") (pintype "input"))
      (node (ref "IC7") (pin "D5") (pinfunction "GND_D5") (pintype "power_in"))
      (node (ref "IC9") (pin "6") (pinfunction "GND_6") (pintype "passive"))
      (node (ref "IC9") (pin "9") (pinfunction "EP_9") (pintype "passive"))
      (node (ref "LD3") (pin "1") (pinfunction "C_1") (pintype "passive"))
      (node (ref "LD8") (pin "1") (pinfunction "C_1") (pintype "passive"))
      (node (ref "R34") (pin "2") (pinfunction "2_2") (pintype "passive"))
      (node (ref "R38") (pin "2") (pinfunction "2_2") (pintype "passive"))
      (node (ref "R45") (pin "1") (pinfunction "1_1") (pintype "passive"))
      (node (ref "R47") (pin "2") (pinfunction "2_2") (pintype "passive"))
      (node (ref "R8") (pin "1") (pinfunction "1_1") (pintype "passive"))
    )
    (net (code "17") (name "N3V0A") (class "Default")
      (node (ref "L30") (pin "2") (pinfunction "2_2") (pintype "passive"))
      (node (ref "TP9") (pin "1") (pinfunction "1_1") (pintype "bidirectional"))
    )
    (net (code "18") (name "Net-(C16-Pad1)") (class "Default")
      (node (ref "C16") (pin "1") (pinfunction "1_1") (pintype "passive"))
      (node (ref "C35") (pin "2") (pinfunction "2_2") (pintype "passive"))
      (node (ref "L29") (pin "2") (pinfunction "2_2") (pintype "passive"))
      (node (ref "L30") (pin "1") (pinfunction "1_1") (pintype "passive"))
    )
    (net (code "19") (name "Net-(IC6-SS)") (class "Default")
      (node (ref "C14") (pin "2") (pinfunction "2_2") (pintype "passive"))
      (node (ref "IC6") (pin "4") (pinfunction "SS_4") (pintype "input"))
    )
    (net (code "20") (name "Net-(IC7-COMP1)") (class "Default")
      (node (ref "IC7") (pin "E5") (pinfunction "COMP1_E5") (pintype "input"))
      (node (ref "TP6") (pin "1") (pinfunction "1_1") (pintype "bidirectional"))
    )
    (net (code "21") (name "Net-(IC7-COMP2)") (class "Default")
      (node (ref "IC7") (pin "A5") (pinfunction "COMP2_A5") (pintype "input"))
      (node (ref "TP7") (pin "1") (pinfunction "1_1") (pintype "bidirectional"))
    )
    (net (code "22") (name "Net-(IC7-FB1)") (class "Default")
      (node (ref "IC7") (pin "E4") (pinfunction "FB1_E4") (pintype "input"))
      (node (ref "R34") (pin "1") (pinfunction "1_1") (pintype "passive"))
    )
    (net (code "23") (name "Net-(IC7-FB2)") (class "Default")
      (node (ref "IC7") (pin "A4") (pinfunction "FB2_A4") (pintype "input"))
      (node (ref "R36") (pin "1") (pinfunction "1_1") (pintype "passive"))
    )
    (net (code "24") (name "Net-(IC7-FREQ)") (class "Default")
      (node (ref "IC7") (pin "C4") (pinfunction "FREQ_C4") (pintype "input"))
      (node (ref "R45") (pin "2") (pinfunction "2_2") (pintype "passive"))
    )
    (net (code "25") (name "Net-(IC7-INTVCC)") (class "Default")
      (node (ref "IC7") (pin "C3") (pinfunction "INTVCC_C3") (pintype "power_in"))
      (node (ref "TP5") (pin "1") (pinfunction "1_1") (pintype "bidirectional"))
    )
    (net (code "26") (name "Net-(IC7-TRACK{slash}SS1)") (class "Default")
      (node (ref "C233") (pin "2") (pinfunction "2_2") (pintype "passive"))
      (node (ref "IC7") (pin "A3") (pinfunction "TRACK/SS2_A3") (pintype "input"))
      (node (ref "IC7") (pin "E3") (pinfunction "TRACK/SS1_E3") (pintype "input"))
    )
    (net (code "27") (name "Net-(IC9-SS)") (class "Default")
      (node (ref "C17") (pin "2") (pinfunction "2_2") (pintype "passive"))
      (node (ref "IC9") (pin "4") (pinfunction "SS_4") (pintype "input"))
    )
    (net (code "28") (name "Net-(IC10-CAP)") (class "Default")
      (node (ref "C239") (pin "2") (pinfunction "2_2") (pintype "passive"))
      (node (ref "IC10") (pin "6") (pinfunction "CAP_6") (pintype "output"))
    )
    (net (code "29") (name "Net-(IC10-CP)") (class "Default")
      (node (ref "C20") (pin "1") (pinfunction "1_1") (pintype "passive"))
      (node (ref "IC10") (pin "11") (pinfunction "CP_11") (pintype "output"))
    )
    (net (code "30") (name "Net-(IC10-FB)") (class "Default")
      (node (ref "IC10") (pin "5") (pinfunction "FB_5") (pintype "input"))
      (node (ref "R46") (pin "2") (pinfunction "2_2") (pintype "passive"))
      (node (ref "R47") (pin "1") (pinfunction "1_1") (pintype "passive"))
    )
    (net (code "31") (name "Net-(IC10-SW)") (class "Default")
      (node (ref "C20") (pin "2") (pinfunction "2_2") (pintype "passive"))
      (node (ref "IC10") (pin "8") (pinfunction "SW_8") (pintype "output"))
      (node (ref "L15") (pin "1") (pinfunction "1_1") (pintype "passive"))
    )
    (net (code "32") (name "Net-(IC10-VAUX)") (class "Default")
      (node (ref "C36") (pin "2") (pinfunction "2_2") (pintype "passive"))
      (node (ref "C38") (pin "2") (pinfunction "2_2") (pintype "passive"))
      (node (ref "IC10") (pin "1") (pinfunction "VAUX_1") (pintype "output"))
    )
    (net (code "33") (name "Net-(IC10-VIN)") (class "Default")
      (node (ref "C15") (pin "2") (pinfunction "2_2") (pintype "passive"))
      (node (ref "C21") (pin "2") (pinfunction "2_2") (pintype "passive"))
      (node (ref "IC10") (pin "12") (pinfunction "VIN_12") (pintype "input"))
      (node (ref "L27") (pin "1") (pinfunction "1_1") (pintype "passive"))
    )
    (net (code "34") (name "Net-(IC10-VREF)") (class "Default")
      (node (ref "IC10") (pin "4") (pinfunction "VREF_4") (pintype "output"))
      (node (ref "R46") (pin "1") (pinfunction "1_1") (pintype "passive"))
    )
    (net (code "35") (name "Net-(IC11-FB)") (class "Default")
      (node (ref "IC11") (pin "5") (pinfunction "FB_5") (pintype "input"))
      (node (ref "R6") (pin "1") (pinfunction "1_1") (pintype "passive"))
      (node (ref "R8") (pin "2") (pinfunction "2_2") (pintype "passive"))
    )
    (net (code "36") (name "Net-(IC11-SW)") (class "Default")
      (node (ref "IC11") (pin "3") (pinfunction "SW_3") (pintype "power_in"))
      (node (ref "L13") (pin "1") (pinfunction "1_1") (pintype "passive"))
    )
    (net (code "37") (name "Net-(IC12-SS)") (class "Default")
      (node (ref "C19") (pin "2") (pinfunction "2_2") (pintype "passive"))
      (node (ref "IC12") (pin "7") (pinfunction "SS_7") (pintype "input"))
    )
    (net (code "38") (name "Net-(IC23-SS)") (class "Default")
      (node (ref "C18") (pin "2") (pinfunction "2_2") (pintype "passive"))
      (node (ref "IC23") (pin "4") (pinfunction "SS_4") (pintype "input"))
    )
    (net (code "39") (name "Net-(LD3-A)") (class "Default")
      (node (ref "LD3") (pin "2") (pinfunction "A_2") (pintype "passive"))
      (node (ref "R11") (pin "1") (pinfunction "1_1") (pintype "passive"))
    )
    (net (code "40") (name "Net-(LD5-A)") (class "Default")
      (node (ref "LD5") (pin "2") (pinfunction "A_2") (pintype "passive"))
      (node (ref "R9") (pin "1") (pinfunction "1_1") (pintype "passive"))
    )
    (net (code "41") (name "Net-(LD8-A)") (class "Default")
      (node (ref "LD8") (pin "2") (pinfunction "A_2") (pintype "passive"))
      (node (ref "R17") (pin "1") (pinfunction "1_1") (pintype "passive"))
    )
    (net (code "42") (name "Net-(R36-Pad2)") (class "Default")
      (node (ref "R36") (pin "2") (pinfunction "2_2") (pintype "passive"))
      (node (ref "R38") (pin "1") (pinfunction "1_1") (pintype "passive"))
    )
    (net (code "43") (name "P1V8") (class "Default")
      (node (ref "C11") (pin "2") (pinfunction "2_2") (pintype "passive"))
      (node (ref "IC12") (pin "10") (pinfunction "VOUT_10") (pintype "power_in"))
      (node (ref "IC12") (pin "11") (pinfunction "VOUT_11") (pintype "power_in"))
      (node (ref "IC12") (pin "12") (pinfunction "VOUT_12") (pintype "power_in"))
      (node (ref "IC12") (pin "13") (pinfunction "VOUT_13") (pintype "power_in"))
      (node (ref "IC12") (pin "14") (pinfunction "VOUT_14") (pintype "power_in"))
      (node (ref "IC12") (pin "9") (pinfunction "SENS_9") (pintype "input"))
      (node (ref "TP8") (pin "1") (pinfunction "1_1") (pintype "bidirectional"))
    )
    (net (code "44") (name "P3V3") (class "Default")
      (node (ref "C8") (pin "2") (pinfunction "2_2") (pintype "passive"))
      (node (ref "IC11") (pin "4") (pinfunction "VIN_4") (pintype "input"))
      (node (ref "L27") (pin "2") (pinfunction "2_2") (pintype "passive"))
      (node (ref "R11") (pin "2") (pinfunction "2_2") (pintype "passive"))
      (node (ref "R14") (pin "1") (pinfunction "1_1") (pintype "passive"))
      (node (ref "R33") (pin "1") (pinfunction "1_1") (pintype "passive"))
      (node (ref "R9") (pin "2") (pinfunction "2_2") (pintype "passive"))
      (node (ref "TP3") (pin "1") (pinfunction "1_1") (pintype "bidirectional"))
    )
    (net (code "45") (name "P3V3A") (class "Default")
      (node (ref "L8") (pin "2") (pinfunction "2_2") (pintype "passive"))
    )
    (net (code "46") (name "P3V3_CLK") (class "Default")
      (node (ref "L5") (pin "2") (pinfunction "2_2") (pintype "passive"))
      (node (ref "TP4") (pin "1") (pinfunction "1_1") (pintype "bidirectional"))
    )
    (net (code "47") (name "P5V0A") (class "Default")
      (node (ref "L9") (pin "2") (pinfunction "2_2") (pintype "passive"))
      (node (ref "TP2") (pin "1") (pinfunction "1_1") (pintype "bidirectional"))
    )
    (net (code "48") (name "P12V0") (class "Default")
      (node (ref "C234") (pin "2") (pinfunction "2_2") (pintype "passive"))
      (node (ref "C235") (pin "2") (pinfunction "2_2") (pintype "passive"))
      (node (ref "IC7") (pin "A2") (pinfunction "VIN1_A2") (pintype "power_in"))
      (node (ref "IC7") (pin "B3") (pinfunction "VIN1_B3") (pintype "power_in"))
      (node (ref "IC7") (pin "D3") (pinfunction "VIN2_D3") (pintype "power_in"))
      (node (ref "IC7") (pin "E2") (pinfunction "VIN2_E2") (pintype "power_in"))
      (node (ref "R17") (pin "2") (pinfunction "2_2") (pintype "passive"))
    )
    (net (code "49") (name "VADJ") (class "Default")
      (node (ref "R49") (pin "1") (pinfunction "1_1") (pintype "passive"))
    )
    (net (code "50") (name "unconnected-(IC12-NC-Pad8)") (class "Default")
      (node (ref "IC12") (pin "8") (pinfunction "NC_8") (pintype "passive"))
    )
  )
)
